# RobomasterHub.net
KiCad netlist of a schematic drawn in EAGLE
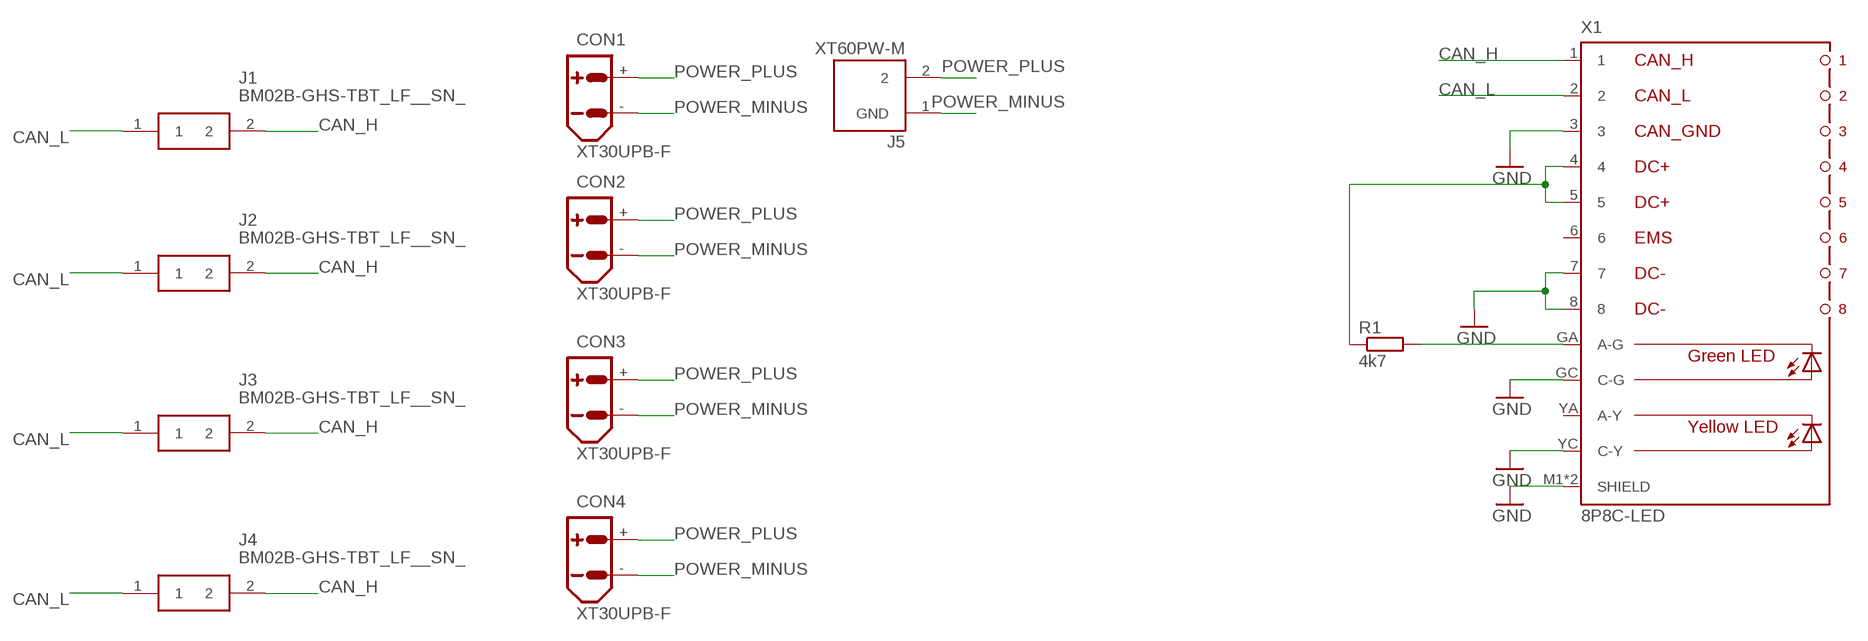
[diagram p0: schematic, sheet 1]

(export (version "E")
  (design (tool "Eeschema 10.0.6"))
  (components
    (comp (ref "CON1")
      (value "XT30UPB-F")
      (footprint "eagle-import:XT30UPB-F")
      (libsource (lib "eagle-import") (part "XT30UPB-F"))
    )
    (comp (ref "CON2")
      (value "XT30UPB-F")
      (footprint "eagle-import:XT30UPB-F")
      (libsource (lib "eagle-import") (part "XT30UPB-F"))
    )
    (comp (ref "CON3")
      (value "XT30UPB-F")
      (footprint "eagle-import:XT30UPB-F")
      (libsource (lib "eagle-import") (part "XT30UPB-F"))
    )
    (comp (ref "CON4")
      (value "XT30UPB-F")
      (footprint "eagle-import:XT30UPB-F")
      (libsource (lib "eagle-import") (part "XT30UPB-F"))
    )
    (comp (ref "J1")
      (value "BM02B-GHS-TBT_LF__SN_")
      (footprint "eagle-import:BM02B-GHS-TBT_1")
      (fields (field (name "MANUFACTURER_PART_NUMBER") "BM02B-GHS-TBT(LF)(SN)"))
      (libsource (lib "eagle-import") (part "BM02B-GHS-TBT_LF__SN_"))
    )
    (comp (ref "J2")
      (value "BM02B-GHS-TBT_LF__SN_")
      (footprint "eagle-import:BM02B-GHS-TBT_1")
      (fields (field (name "MANUFACTURER_PART_NUMBER") "BM02B-GHS-TBT(LF)(SN)"))
      (libsource (lib "eagle-import") (part "BM02B-GHS-TBT_LF__SN_"))
    )
    (comp (ref "J3")
      (value "BM02B-GHS-TBT_LF__SN_")
      (footprint "eagle-import:BM02B-GHS-TBT_1")
      (fields (field (name "MANUFACTURER_PART_NUMBER") "BM02B-GHS-TBT(LF)(SN)"))
      (libsource (lib "eagle-import") (part "BM02B-GHS-TBT_LF__SN_"))
    )
    (comp (ref "J4")
      (value "BM02B-GHS-TBT_LF__SN_")
      (footprint "eagle-import:BM02B-GHS-TBT_1")
      (fields (field (name "MANUFACTURER_PART_NUMBER") "BM02B-GHS-TBT(LF)(SN)"))
      (libsource (lib "eagle-import") (part "BM02B-GHS-TBT_LF__SN_"))
    )
    (comp (ref "J5")
      (value "XT60PW-M")
      (footprint "eagle-import:AMASS_XT60PW-M")
      (fields (field (name "MF") "AMASS") (field (name "MP") "XT60PW-M "))
      (libsource (lib "eagle-import") (part "XT60PW-M"))
    )
    (comp (ref "R1")
      (value "4k7")
      (footprint "eagle-import:R0603")
      (libsource (lib "eagle-import") (part "R-EU_R0603"))
    )
    (comp (ref "X1")
      (value "8P8C-LED")
      (footprint "eagle-import:8P8C-LED")
      (libsource (lib "eagle-import") (part "8P8C-LED"))
    )
  )
  (nets
    (net (code "1") (name "/CAN_H") (class "Default")
      (node (ref "J1") (pin "2") (pinfunction "2_2") (pintype "bidirectional"))
      (node (ref "J2") (pin "2") (pinfunction "2_2") (pintype "bidirectional"))
      (node (ref "J3") (pin "2") (pinfunction "2_2") (pintype "bidirectional"))
      (node (ref "J4") (pin "2") (pinfunction "2_2") (pintype "bidirectional"))
      (node (ref "X1") (pin "1") (pinfunction "1_1") (pintype "input"))
    )
    (net (code "2") (name "/CAN_L") (class "Default")
      (node (ref "J1") (pin "1") (pinfunction "1_1") (pintype "bidirectional"))
      (node (ref "J2") (pin "1") (pinfunction "1_1") (pintype "bidirectional"))
      (node (ref "J3") (pin "1") (pinfunction "1_1") (pintype "bidirectional"))
      (node (ref "J4") (pin "1") (pinfunction "1_1") (pintype "bidirectional"))
      (node (ref "X1") (pin "2") (pinfunction "2_2") (pintype "input"))
    )
    (net (code "3") (name "/POWER_MINUS") (class "Default")
      (node (ref "CON1") (pin "-") (pinfunction "-_-") (pintype "power_in"))
      (node (ref "CON2") (pin "-") (pinfunction "-_-") (pintype "power_in"))
      (node (ref "CON3") (pin "-") (pinfunction "-_-") (pintype "power_in"))
      (node (ref "CON4") (pin "-") (pinfunction "-_-") (pintype "power_in"))
      (node (ref "J5") (pin "1") (pinfunction "GND_1") (pintype "passive"))
    )
    (net (code "4") (name "/POWER_PLUS") (class "Default")
      (node (ref "CON1") (pin "+") (pinfunction "+_+") (pintype "power_in"))
      (node (ref "CON2") (pin "+") (pinfunction "+_+") (pintype "power_in"))
      (node (ref "CON3") (pin "+") (pinfunction "+_+") (pintype "power_in"))
      (node (ref "CON4") (pin "+") (pinfunction "+_+") (pintype "power_in"))
      (node (ref "J5") (pin "2") (pinfunction "2_2") (pintype "passive"))
    )
    (net (code "5") (name "GND") (class "Default")
      (node (ref "X1") (pin "3") (pinfunction "3_3") (pintype "input"))
      (node (ref "X1") (pin "7") (pinfunction "7_7") (pintype "input"))
      (node (ref "X1") (pin "8") (pinfunction "8_8") (pintype "input"))
      (node (ref "X1") (pin "GC") (pinfunction "C-G_GC") (pintype "passive"))
      (node (ref "X1") (pin "M1") (pinfunction "SHIELD_M1") (pintype "passive"))
      (node (ref "X1") (pin "M2") (pinfunction "SHIELD_M2") (pintype "passive"))
      (node (ref "X1") (pin "YC") (pinfunction "C-Y_YC") (pintype "passive"))
    )
    (net (code "6") (name "Net-(R1-Pad1)") (class "Default")
      (node (ref "R1") (pin "1") (pinfunction "1_1") (pintype "passive"))
      (node (ref "X1") (pin "4") (pinfunction "4_4") (pintype "input"))
      (node (ref "X1") (pin "5") (pinfunction "5_5") (pintype "input"))
    )
    (net (code "7") (name "Net-(X1-A-G)") (class "Default")
      (node (ref "R1") (pin "2") (pinfunction "2_2") (pintype "passive"))
      (node (ref "X1") (pin "GA") (pinfunction "A-G_GA") (pintype "passive"))
    )
    (net (code "8") (name "unconnected-(X1-A-Y-PadYA)") (class "Default")
      (node (ref "X1") (pin "YA") (pinfunction "A-Y_YA") (pintype "passive"))
    )
    (net (code "9") (name "unconnected-(X1-Pad6)") (class "Default")
      (node (ref "X1") (pin "6") (pinfunction "6_6") (pintype "input"))
    )
  )
)
